# untitled.net
KiCad netlist of a schematic drawn in EAGLE
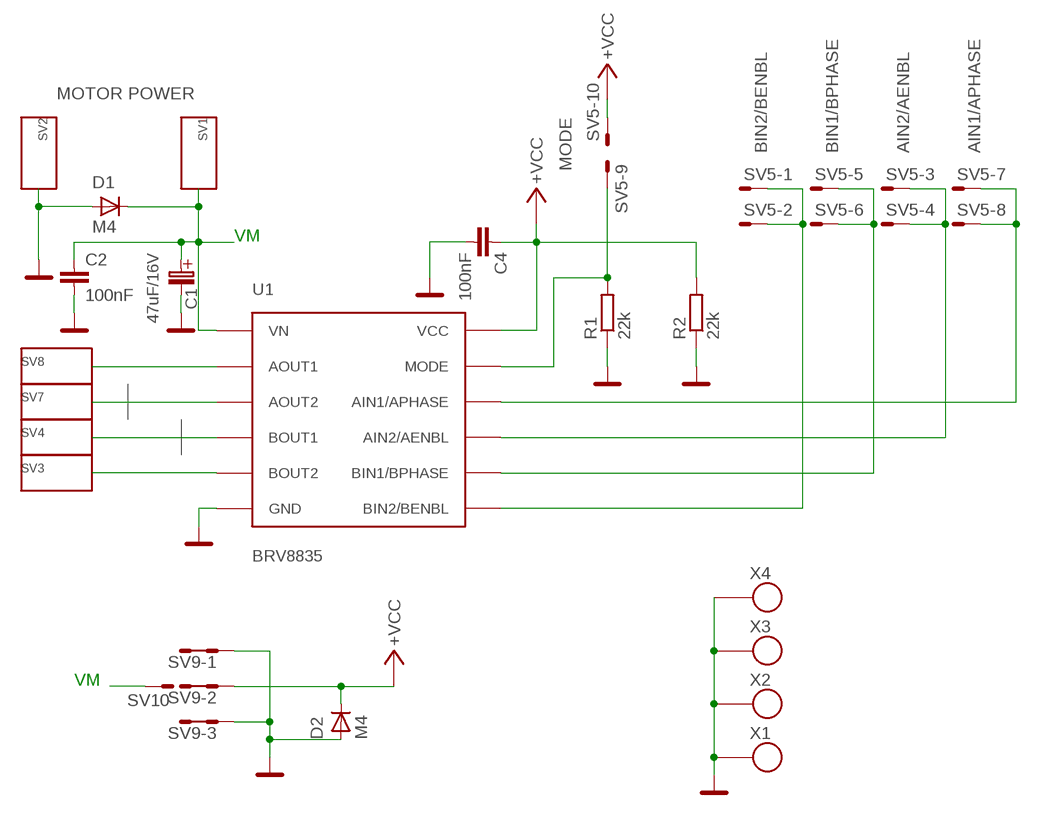
[diagram p0: schematic, sheet 1]

(export (version "E")
  (design (tool "Eeschema 10.0.6"))
  (components
    (comp (ref "C1")
      (value "47uF/16V")
      (footprint "eagle-import:C")
      (libsource (lib "eagle-import") (part "C"))
    )
    (comp (ref "C2")
      (value "100nF")
      (footprint "eagle-import:C0805")
      (libsource (lib "eagle-import") (part "C0805"))
    )
    (comp (ref "C4")
      (value "100nF")
      (footprint "eagle-import:C0805")
      (libsource (lib "eagle-import") (part "C0805"))
    )
    (comp (ref "D1")
      (value "M4")
      (footprint "eagle-import:SMA")
      (libsource (lib "eagle-import") (part "D-OB.SMA"))
    )
    (comp (ref "D2")
      (value "M4")
      (footprint "eagle-import:SMA")
      (libsource (lib "eagle-import") (part "D-OB.SMA"))
    )
    (comp (ref "R1")
      (value "22k")
      (footprint "eagle-import:0805")
      (libsource (lib "eagle-import") (part "R0805"))
    )
    (comp (ref "R2")
      (value "22k")
      (footprint "eagle-import:0805")
      (libsource (lib "eagle-import") (part "R0805"))
    )
    (comp (ref "SV1")
      (value "WAGO256")
      (footprint "eagle-import:WAGO256")
      (libsource (lib "eagle-import") (part "WAGO256"))
    )
    (comp (ref "SV2")
      (value "WAGO256")
      (footprint "eagle-import:WAGO256")
      (libsource (lib "eagle-import") (part "WAGO256"))
    )
    (comp (ref "SV3")
      (value "WAGO256")
      (footprint "eagle-import:WAGO256")
      (libsource (lib "eagle-import") (part "WAGO256"))
    )
    (comp (ref "SV4")
      (value "WAGO256")
      (footprint "eagle-import:WAGO256")
      (libsource (lib "eagle-import") (part "WAGO256"))
    )
    (comp (ref "SV5")
      (value "MA05-3")
      (footprint "eagle-import:MA05-2")
      (libsource (lib "eagle-import") (part "MA05-3"))
    )
    (comp (ref "SV7")
      (value "WAGO256")
      (footprint "eagle-import:WAGO256")
      (libsource (lib "eagle-import") (part "WAGO256"))
    )
    (comp (ref "SV8")
      (value "WAGO256")
      (footprint "eagle-import:WAGO256")
      (libsource (lib "eagle-import") (part "WAGO256"))
    )
    (comp (ref "SV9")
      (value "MA03-2")
      (footprint "eagle-import:MA03-2")
      (libsource (lib "eagle-import") (part "MA03-2"))
    )
    (comp (ref "SV10")
      (value "MA01-1")
      (footprint "eagle-import:MA01-1")
      (libsource (lib "eagle-import") (part "MA01-1"))
    )
    (comp (ref "U1")
      (value "BRV8835")
      (footprint "eagle-import:WSON")
      (libsource (lib "eagle-import") (part "DRV8835"))
    )
    (comp (ref "X1")
      (value "SROUB3M")
      (footprint "eagle-import:SROUB3M")
      (libsource (lib "eagle-import") (part "SROUB3M"))
    )
    (comp (ref "X2")
      (value "SROUB3M")
      (footprint "eagle-import:SROUB3M")
      (libsource (lib "eagle-import") (part "SROUB3M"))
    )
    (comp (ref "X3")
      (value "SROUB3M")
      (footprint "eagle-import:SROUB3M")
      (libsource (lib "eagle-import") (part "SROUB3M"))
    )
    (comp (ref "X4")
      (value "SROUB3M")
      (footprint "eagle-import:SROUB3M")
      (libsource (lib "eagle-import") (part "SROUB3M"))
    )
  )
  (nets
    (net (code "1") (name "+VCC") (class "Default")
      (node (ref "C4") (pin "1") (pinfunction "1_1") (pintype "passive"))
      (node (ref "D2") (pin "K") (pinfunction "C_K") (pintype "passive"))
      (node (ref "R2") (pin "2") (pinfunction "2_2") (pintype "passive"))
      (node (ref "SV5") (pin "10") (pinfunction "P$1_10") (pintype "passive"))
      (node (ref "SV9") (pin "3") (pinfunction "K_3") (pintype "passive"))
      (node (ref "SV9") (pin "4") (pinfunction "K_4") (pintype "passive"))
      (node (ref "U1") (pin "12") (pinfunction "VCC_12") (pintype "bidirectional"))
    )
    (net (code "2") (name "/VN") (class "Default")
      (node (ref "C1") (pin "+") (pinfunction "C_EL+_+") (pintype "passive"))
      (node (ref "C2") (pin "1") (pinfunction "1_1") (pintype "passive"))
      (node (ref "D1") (pin "K") (pinfunction "C_K") (pintype "passive"))
      (node (ref "SV1") (pin "1") (pinfunction "P$1_1") (pintype "passive"))
      (node (ref "SV1") (pin "A1") (pinfunction "P$1_A1") (pintype "passive"))
      (node (ref "SV10") (pin "1") (pinfunction "P$1_1") (pintype "passive"))
      (node (ref "U1") (pin "1") (pinfunction "VN_1") (pintype "bidirectional"))
    )
    (net (code "3") (name "GND") (class "Default")
      (node (ref "C1") (pin "-") (pinfunction "C_EL-_-") (pintype "passive"))
      (node (ref "C2") (pin "2") (pinfunction "2_2") (pintype "passive"))
      (node (ref "C4") (pin "2") (pinfunction "2_2") (pintype "passive"))
      (node (ref "D1") (pin "A") (pinfunction "A_A") (pintype "passive"))
      (node (ref "D2") (pin "A") (pinfunction "A_A") (pintype "passive"))
      (node (ref "R1") (pin "1") (pinfunction "1_1") (pintype "passive"))
      (node (ref "R2") (pin "1") (pinfunction "1_1") (pintype "passive"))
      (node (ref "SV2") (pin "1") (pinfunction "P$1_1") (pintype "passive"))
      (node (ref "SV2") (pin "A1") (pinfunction "P$1_A1") (pintype "passive"))
      (node (ref "SV9") (pin "1") (pinfunction "K_1") (pintype "passive"))
      (node (ref "SV9") (pin "2") (pinfunction "K_2") (pintype "passive"))
      (node (ref "SV9") (pin "5") (pinfunction "K_5") (pintype "passive"))
      (node (ref "SV9") (pin "6") (pinfunction "K_6") (pintype "passive"))
      (node (ref "U1") (pin "6") (pinfunction "GND_6") (pintype "bidirectional"))
      (node (ref "U1") (pin "P1") (pinfunction "GND_P1") (pintype "bidirectional"))
      (node (ref "U1") (pin "P2") (pinfunction "GND_P2") (pintype "bidirectional"))
      (node (ref "U1") (pin "P3") (pinfunction "GND_P3") (pintype "bidirectional"))
      (node (ref "U1") (pin "P4") (pinfunction "GND_P4") (pintype "bidirectional"))
      (node (ref "U1") (pin "P5") (pinfunction "GND_P5") (pintype "bidirectional"))
      (node (ref "U1") (pin "P6") (pinfunction "GND_P6") (pintype "bidirectional"))
      (node (ref "U1") (pin "P7") (pinfunction "GND_P7") (pintype "bidirectional"))
      (node (ref "U1") (pin "P8") (pinfunction "GND_P8") (pintype "bidirectional"))
      (node (ref "X1") (pin "P$1") (pinfunction "P$1_P$1") (pintype "bidirectional"))
      (node (ref "X2") (pin "P$1") (pinfunction "P$1_P$1") (pintype "bidirectional"))
      (node (ref "X3") (pin "P$1") (pinfunction "P$1_P$1") (pintype "bidirectional"))
      (node (ref "X4") (pin "P$1") (pinfunction "P$1_P$1") (pintype "bidirectional"))
    )
    (net (code "4") (name "Net-(SV5A-P$1)") (class "Default")
      (node (ref "SV5") (pin "1") (pinfunction "P$1_1") (pintype "passive"))
      (node (ref "SV5") (pin "2") (pinfunction "P$1_2") (pintype "passive"))
      (node (ref "U1") (pin "7") (pinfunction "BIN2/BENBL_7") (pintype "bidirectional"))
    )
    (net (code "5") (name "Net-(SV5D-P$1)") (class "Default")
      (node (ref "SV5") (pin "3") (pinfunction "P$1_3") (pintype "passive"))
      (node (ref "SV5") (pin "4") (pinfunction "P$1_4") (pintype "passive"))
      (node (ref "U1") (pin "9") (pinfunction "AIN2/AENBL_9") (pintype "bidirectional"))
    )
    (net (code "6") (name "Net-(SV5F-P$1)") (class "Default")
      (node (ref "SV5") (pin "5") (pinfunction "P$1_5") (pintype "passive"))
      (node (ref "SV5") (pin "6") (pinfunction "P$1_6") (pintype "passive"))
      (node (ref "U1") (pin "8") (pinfunction "BIN1/BPHASE_8") (pintype "bidirectional"))
    )
    (net (code "7") (name "Net-(SV5H-P$1)") (class "Default")
      (node (ref "SV5") (pin "7") (pinfunction "P$1_7") (pintype "passive"))
      (node (ref "SV5") (pin "8") (pinfunction "P$1_8") (pintype "passive"))
      (node (ref "U1") (pin "10") (pinfunction "AIN1/APHASE_10") (pintype "bidirectional"))
    )
    (net (code "8") (name "Net-(SV5J-P$1)") (class "Default")
      (node (ref "R1") (pin "2") (pinfunction "2_2") (pintype "passive"))
      (node (ref "SV5") (pin "9") (pinfunction "P$1_9") (pintype "passive"))
      (node (ref "U1") (pin "11") (pinfunction "MODE_11") (pintype "bidirectional"))
    )
    (net (code "9") (name "Net-(U1-AOUT1)") (class "Default")
      (node (ref "SV8") (pin "1") (pinfunction "P$1_1") (pintype "passive"))
      (node (ref "SV8") (pin "A1") (pinfunction "P$1_A1") (pintype "passive"))
      (node (ref "U1") (pin "2") (pinfunction "AOUT1_2") (pintype "bidirectional"))
    )
    (net (code "10") (name "Net-(U1-AOUT2)") (class "Default")
      (node (ref "SV7") (pin "1") (pinfunction "P$1_1") (pintype "passive"))
      (node (ref "SV7") (pin "A1") (pinfunction "P$1_A1") (pintype "passive"))
      (node (ref "U1") (pin "3") (pinfunction "AOUT2_3") (pintype "bidirectional"))
    )
    (net (code "11") (name "Net-(U1-BOUT1)") (class "Default")
      (node (ref "SV4") (pin "1") (pinfunction "P$1_1") (pintype "passive"))
      (node (ref "SV4") (pin "A1") (pinfunction "P$1_A1") (pintype "passive"))
      (node (ref "U1") (pin "4") (pinfunction "BOUT1_4") (pintype "bidirectional"))
    )
    (net (code "12") (name "Net-(U1-BOUT2)") (class "Default")
      (node (ref "SV3") (pin "1") (pinfunction "P$1_1") (pintype "passive"))
      (node (ref "SV3") (pin "A1") (pinfunction "P$1_A1") (pintype "passive"))
      (node (ref "U1") (pin "5") (pinfunction "BOUT2_5") (pintype "bidirectional"))
    )
  )
)
